# vader.net
KiCad netlist of a schematic drawn in EAGLE
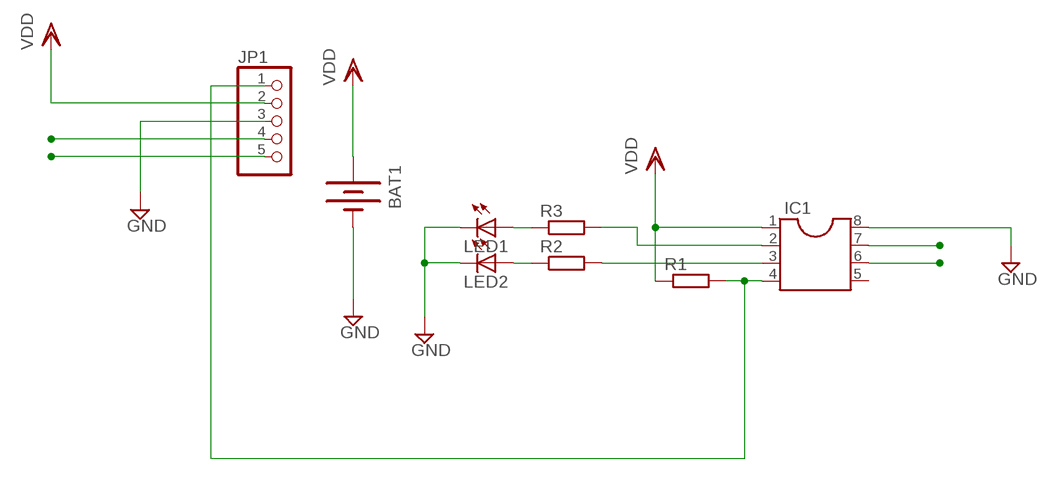
[diagram p0: schematic, sheet 1]

(export (version "E")
  (design (tool "Eeschema 10.0.6"))
  (components
    (comp (ref "BAT1")
      (value "BATTERY20PTH")
      (footprint "eagle-import:BATTCOM_20MM_PTH")
      (libsource (lib "eagle-import") (part "BATTERY20PTH"))
    )
    (comp (ref "IC1")
      (value "DIL8S")
      (footprint "eagle-import:SOCKET-08")
      (libsource (lib "eagle-import") (part "DIL8S"))
    )
    (comp (ref "JP1")
      (value "PINHD-1X5")
      (footprint "eagle-import:1X05")
      (libsource (lib "eagle-import") (part "PINHD-1X5"))
    )
    (comp (ref "LED1")
      (value "LED3MM")
      (footprint "eagle-import:LED3MM")
      (libsource (lib "eagle-import") (part "LED3MM"))
    )
    (comp (ref "LED2")
      (value "LED3MM")
      (footprint "eagle-import:LED3MM")
      (libsource (lib "eagle-import") (part "LED3MM"))
    )
    (comp (ref "R1")
      (value "R-EU_0204/7")
      (footprint "eagle-import:0204_7")
      (libsource (lib "eagle-import") (part "R-EU_0204/7"))
    )
    (comp (ref "R2")
      (value "R-EU_0204/7")
      (footprint "eagle-import:0204_7")
      (libsource (lib "eagle-import") (part "R-EU_0204/7"))
    )
    (comp (ref "R3")
      (value "R-EU_0204/7")
      (footprint "eagle-import:0204_7")
      (libsource (lib "eagle-import") (part "R-EU_0204/7"))
    )
  )
  (nets
    (net (code "1") (name "/ICSPCLK") (class "Default")
      (node (ref "IC1") (pin "6") (pinfunction "6_6") (pintype "passive"))
      (node (ref "JP1") (pin "5") (pinfunction "5_5") (pintype "passive"))
    )
    (net (code "2") (name "/ICSPDAT") (class "Default")
      (node (ref "IC1") (pin "7") (pinfunction "7_7") (pintype "passive"))
      (node (ref "JP1") (pin "4") (pinfunction "4_4") (pintype "passive"))
    )
    (net (code "3") (name "GND") (class "Default")
      (node (ref "BAT1") (pin "2") (pinfunction "-_2") (pintype "power_in"))
      (node (ref "IC1") (pin "8") (pinfunction "8_8") (pintype "passive"))
      (node (ref "JP1") (pin "3") (pinfunction "3_3") (pintype "passive"))
      (node (ref "LED1") (pin "K") (pinfunction "C_K") (pintype "passive"))
      (node (ref "LED2") (pin "K") (pinfunction "C_K") (pintype "passive"))
    )
    (net (code "4") (name "Net-(IC1-Pad2)") (class "Default")
      (node (ref "IC1") (pin "2") (pinfunction "2_2") (pintype "passive"))
      (node (ref "R3") (pin "2") (pinfunction "2_2") (pintype "passive"))
    )
    (net (code "5") (name "Net-(IC1-Pad3)") (class "Default")
      (node (ref "IC1") (pin "3") (pinfunction "3_3") (pintype "passive"))
      (node (ref "R2") (pin "2") (pinfunction "2_2") (pintype "passive"))
    )
    (net (code "6") (name "Net-(IC1-Pad4)") (class "Default")
      (node (ref "IC1") (pin "4") (pinfunction "4_4") (pintype "passive"))
      (node (ref "JP1") (pin "1") (pinfunction "1_1") (pintype "passive"))
      (node (ref "R1") (pin "2") (pinfunction "2_2") (pintype "passive"))
    )
    (net (code "7") (name "Net-(LED1-PadA)") (class "Default")
      (node (ref "LED1") (pin "A") (pinfunction "A_A") (pintype "passive"))
      (node (ref "R3") (pin "1") (pinfunction "1_1") (pintype "passive"))
    )
    (net (code "8") (name "Net-(LED2-PadA)") (class "Default")
      (node (ref "LED2") (pin "A") (pinfunction "A_A") (pintype "passive"))
      (node (ref "R2") (pin "1") (pinfunction "1_1") (pintype "passive"))
    )
    (net (code "9") (name "VDD") (class "Default")
      (node (ref "BAT1") (pin "1") (pinfunction "+_1") (pintype "power_in"))
      (node (ref "IC1") (pin "1") (pinfunction "1_1") (pintype "passive"))
      (node (ref "JP1") (pin "2") (pinfunction "2_2") (pintype "passive"))
      (node (ref "R1") (pin "1") (pinfunction "1_1") (pintype "passive"))
    )
    (net (code "10") (name "unconnected-(IC1-Pad5)") (class "Default")
      (node (ref "IC1") (pin "5") (pinfunction "5_5") (pintype "passive"))
    )
  )
)
